# Primary_MCU.net
KiCad netlist of a schematic drawn in Altium Designer
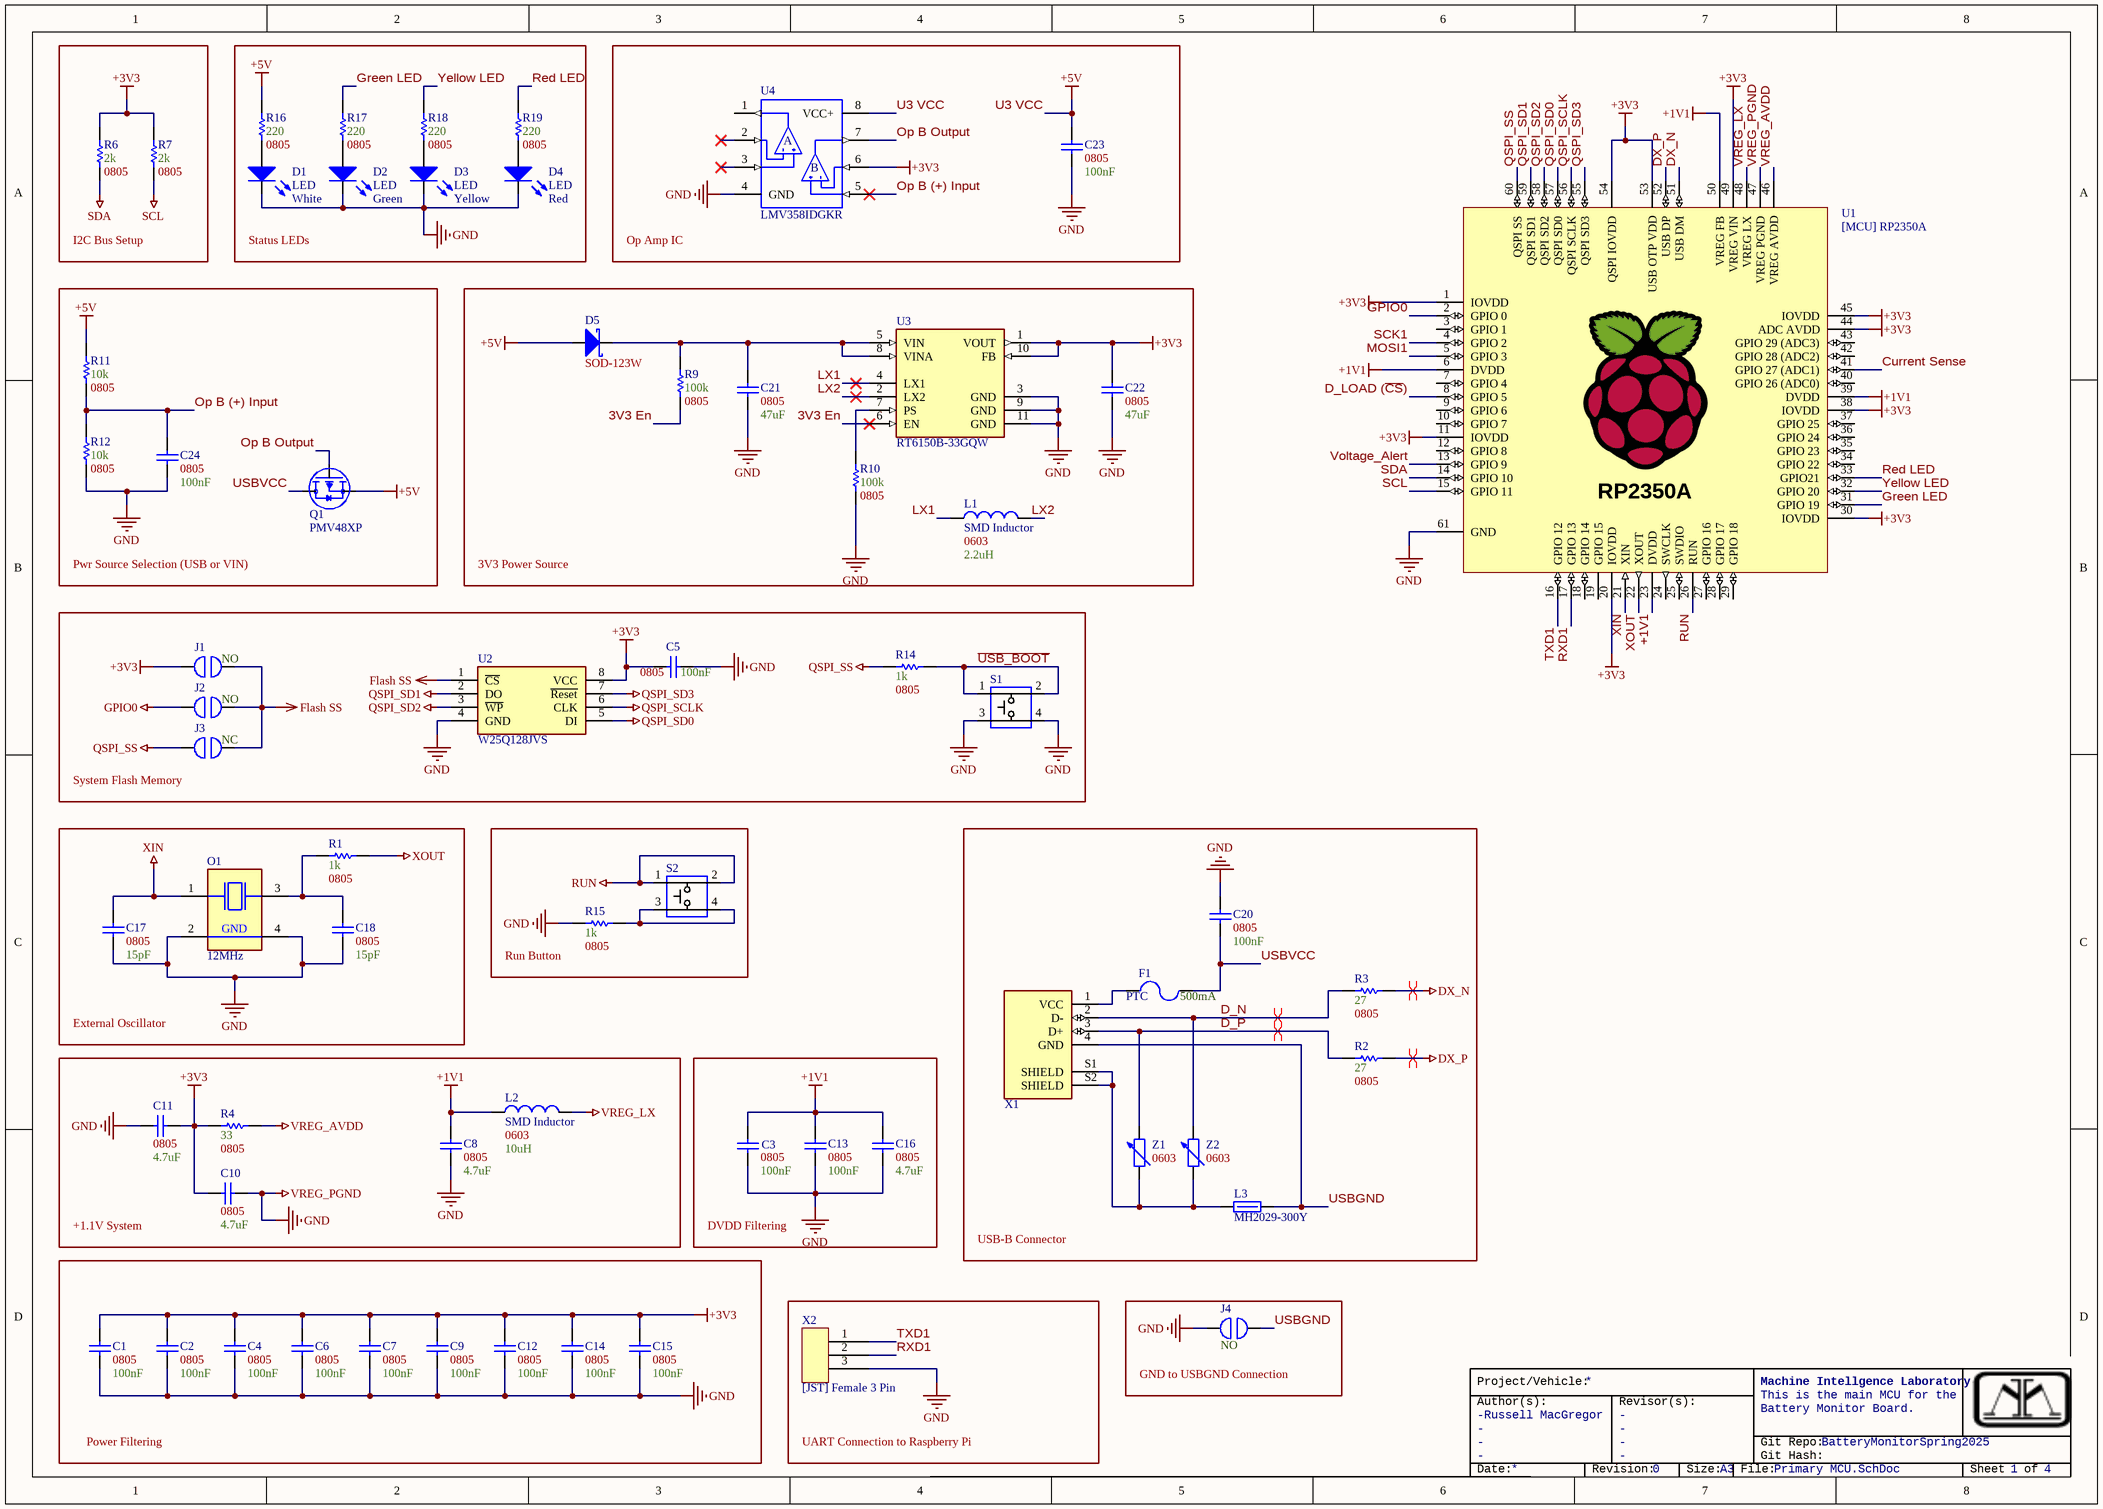
[diagram p0: Primary MCU.SchDoc]

(export (version "E")
  (design (tool "Eeschema 10.0.6"))
  (components
    (comp (ref "C1")
      (value "[Cap] SMD Nonpolarized")
      (footprint "[Cap] SMD 0805")
      (fields (field (name "SIZE PACKAGE") "0805") (field (name "CAPACITANCE") "100nF"))
      (libsource (lib "RADM Components") (part "[Cap] SMD Nonpolarized"))
    )
    (comp (ref "C2")
      (value "[Cap] SMD Nonpolarized")
      (footprint "[Cap] SMD 0805")
      (fields (field (name "SIZE PACKAGE") "0805") (field (name "CAPACITANCE") "100nF"))
      (libsource (lib "RADM Components") (part "[Cap] SMD Nonpolarized"))
    )
    (comp (ref "C3")
      (value "[Cap] SMD Nonpolarized")
      (footprint "[Cap] SMD 0805")
      (fields (field (name "SIZE PACKAGE") "0805") (field (name "CAPACITANCE") "100nF"))
      (libsource (lib "RADM Components") (part "[Cap] SMD Nonpolarized"))
    )
    (comp (ref "C4")
      (value "[Cap] SMD Nonpolarized")
      (footprint "[Cap] SMD 0805")
      (fields (field (name "SIZE PACKAGE") "0805") (field (name "CAPACITANCE") "100nF"))
      (libsource (lib "RADM Components") (part "[Cap] SMD Nonpolarized"))
    )
    (comp (ref "C5")
      (value "[Cap] SMD Nonpolarized")
      (footprint "[Cap] SMD 0805")
      (fields (field (name "SIZE PACKAGE") "0805") (field (name "CAPACITANCE") "100nF"))
      (libsource (lib "RADM Components") (part "[Cap] SMD Nonpolarized"))
    )
    (comp (ref "C6")
      (value "[Cap] SMD Nonpolarized")
      (footprint "[Cap] SMD 0805")
      (fields (field (name "SIZE PACKAGE") "0805") (field (name "CAPACITANCE") "100nF"))
      (libsource (lib "RADM Components") (part "[Cap] SMD Nonpolarized"))
    )
    (comp (ref "C7")
      (value "[Cap] SMD Nonpolarized")
      (footprint "[Cap] SMD 0805")
      (fields (field (name "SIZE PACKAGE") "0805") (field (name "CAPACITANCE") "100nF"))
      (libsource (lib "RADM Components") (part "[Cap] SMD Nonpolarized"))
    )
    (comp (ref "C8")
      (value "[Cap] SMD Nonpolarized")
      (footprint "[Cap] SMD 0805")
      (fields (field (name "SIZE PACKAGE") "0805") (field (name "CAPACITANCE") "4.7uF"))
      (libsource (lib "RADM Components") (part "[Cap] SMD Nonpolarized"))
    )
    (comp (ref "C9")
      (value "[Cap] SMD Nonpolarized")
      (footprint "[Cap] SMD 0805")
      (fields (field (name "SIZE PACKAGE") "0805") (field (name "CAPACITANCE") "100nF"))
      (libsource (lib "RADM Components") (part "[Cap] SMD Nonpolarized"))
    )
    (comp (ref "C10")
      (value "[Cap] SMD Nonpolarized")
      (footprint "[Cap] SMD 0805")
      (fields (field (name "SIZE PACKAGE") "0805") (field (name "CAPACITANCE") "4.7uF"))
      (libsource (lib "RADM Components") (part "[Cap] SMD Nonpolarized"))
    )
    (comp (ref "C11")
      (value "[Cap] SMD Nonpolarized")
      (footprint "[Cap] SMD 0805")
      (fields (field (name "SIZE PACKAGE") "0805") (field (name "CAPACITANCE") "4.7uF"))
      (libsource (lib "RADM Components") (part "[Cap] SMD Nonpolarized"))
    )
    (comp (ref "C12")
      (value "[Cap] SMD Nonpolarized")
      (footprint "[Cap] SMD 0805")
      (fields (field (name "SIZE PACKAGE") "0805") (field (name "CAPACITANCE") "100nF"))
      (libsource (lib "RADM Components") (part "[Cap] SMD Nonpolarized"))
    )
    (comp (ref "C13")
      (value "[Cap] SMD Nonpolarized")
      (footprint "[Cap] SMD 0805")
      (fields (field (name "SIZE PACKAGE") "0805") (field (name "CAPACITANCE") "100nF"))
      (libsource (lib "RADM Components") (part "[Cap] SMD Nonpolarized"))
    )
    (comp (ref "C14")
      (value "[Cap] SMD Nonpolarized")
      (footprint "[Cap] SMD 0805")
      (fields (field (name "SIZE PACKAGE") "0805") (field (name "CAPACITANCE") "100nF"))
      (libsource (lib "RADM Components") (part "[Cap] SMD Nonpolarized"))
    )
    (comp (ref "C15")
      (value "[Cap] SMD Nonpolarized")
      (footprint "[Cap] SMD 0805")
      (fields (field (name "SIZE PACKAGE") "0805") (field (name "CAPACITANCE") "100nF"))
      (libsource (lib "RADM Components") (part "[Cap] SMD Nonpolarized"))
    )
    (comp (ref "C16")
      (value "[Cap] SMD Nonpolarized")
      (footprint "[Cap] SMD 0805")
      (fields (field (name "SIZE PACKAGE") "0805") (field (name "CAPACITANCE") "4.7uF"))
      (libsource (lib "RADM Components") (part "[Cap] SMD Nonpolarized"))
    )
    (comp (ref "C17")
      (value "[Cap] SMD Nonpolarized")
      (footprint "[Cap] SMD 0805")
      (fields (field (name "SIZE PACKAGE") "0805") (field (name "CAPACITANCE") "15pF"))
      (libsource (lib "RADM Components") (part "[Cap] SMD Nonpolarized"))
    )
    (comp (ref "C18")
      (value "[Cap] SMD Nonpolarized")
      (footprint "[Cap] SMD 0805")
      (fields (field (name "SIZE PACKAGE") "0805") (field (name "CAPACITANCE") "15pF"))
      (libsource (lib "RADM Components") (part "[Cap] SMD Nonpolarized"))
    )
    (comp (ref "C20")
      (value "[Cap] SMD Nonpolarized")
      (footprint "[Cap] SMD 0805")
      (fields (field (name "SIZE PACKAGE") "0805") (field (name "CAPACITANCE") "100nF"))
      (libsource (lib "RADM Components") (part "[Cap] SMD Nonpolarized"))
    )
    (comp (ref "C21")
      (value "[Cap] SMD Nonpolarized")
      (footprint "[Cap] SMD 0805")
      (fields (field (name "SIZE PACKAGE") "0805") (field (name "CAPACITANCE") "47uF"))
      (libsource (lib "RADM Components") (part "[Cap] SMD Nonpolarized"))
    )
    (comp (ref "C22")
      (value "[Cap] SMD Nonpolarized")
      (footprint "[Cap] SMD 0805")
      (fields (field (name "SIZE PACKAGE") "0805") (field (name "CAPACITANCE") "47uF"))
      (libsource (lib "RADM Components") (part "[Cap] SMD Nonpolarized"))
    )
    (comp (ref "C23")
      (value "[Cap] SMD Nonpolarized")
      (footprint "[Cap] SMD 0805")
      (fields (field (name "SIZE PACKAGE") "0805") (field (name "CAPACITANCE") "100nF"))
      (libsource (lib "RADM Components") (part "[Cap] SMD Nonpolarized"))
    )
    (comp (ref "C24")
      (value "[Cap] SMD Nonpolarized")
      (footprint "[Cap] SMD 0805")
      (fields (field (name "SIZE PACKAGE") "0805") (field (name "CAPACITANCE") "100nF"))
      (libsource (lib "RADM Components") (part "[Cap] SMD Nonpolarized"))
    )
    (comp (ref "D1")
      (value "LED")
      (footprint "[LED] Thru-Hole, 3mm, White")
      (description "3mm LED")
      (fields (field (name "COLOR") "White"))
      (libsource (lib "RADM Components") (part "[LED] Thru-Hole 3mm"))
    )
    (comp (ref "D2")
      (value "LED")
      (footprint "[LED] Thru-Hole, 3mm, Green")
      (description "3mm LED")
      (fields (field (name "COLOR") "Green"))
      (libsource (lib "RADM Components") (part "[LED] Thru-Hole 3mm"))
    )
    (comp (ref "D3")
      (value "LED")
      (footprint "[LED] Thru-Hole, 3mm, Yellow")
      (description "3mm LED")
      (fields (field (name "COLOR") "Yellow"))
      (libsource (lib "RADM Components") (part "[LED] Thru-Hole 3mm"))
    )
    (comp (ref "D4")
      (value "LED")
      (footprint "[LED] Thru-Hole, 3mm, Red")
      (description "3mm LED")
      (fields (field (name "COLOR") "Red"))
      (libsource (lib "RADM Components") (part "[LED] Thru-Hole 3mm"))
    )
    (comp (ref "D5")
      (value "Schottky")
      (footprint "[Diode] SMD SOD-123W")
      (description "PMEG6010ELR")
      (fields (field (name "SIZE PACKAGE") "SOD-123W"))
      (libsource (lib "RADM Components") (part "[Diode] SMD Schottky"))
    )
    (comp (ref "F1")
      (value "PTC")
      (footprint "[PTC] 500mA Trip")
      (description "MF-MSMF050-2\r\nJLC Part #: C17313")
      (fields (field (name "JLC PART #") "C17313") (field (name "TRIP CURRENT") "500mA"))
      (libsource (lib "RADM Components") (part "[PTC] 500mA Trip"))
    )
    (comp (ref "J1")
      (value "[Jump] SMD Jumper")
      (footprint "[Jumper] Solderable Jumper")
      (description "Solderable jumper")
      (fields (field (name "NO/NC") "NO"))
      (libsource (lib "RADM Components") (part "[Jump] SMD Jumper"))
    )
    (comp (ref "J2")
      (value "[Jump] SMD Jumper")
      (footprint "[Jumper] Solderable Jumper")
      (description "Solderable jumper")
      (fields (field (name "NO/NC") "NO"))
      (libsource (lib "RADM Components") (part "[Jump] SMD Jumper"))
    )
    (comp (ref "J3")
      (value "[Jump] SMD Jumper")
      (footprint "[Jumper] Solderable Jumper")
      (description "Solderable jumper")
      (fields (field (name "NO/NC") "NC"))
      (libsource (lib "RADM Components") (part "[Jump] SMD Jumper"))
    )
    (comp (ref "J4")
      (value "[Jump] SMD Jumper")
      (footprint "[Jumper] Solderable Jumper")
      (description "Solderable jumper")
      (fields (field (name "NO/NC") "NO"))
      (libsource (lib "RADM Components") (part "[Jump] SMD Jumper"))
    )
    (comp (ref "L1")
      (value "SMD Inductor")
      (footprint "[Inductor] SMD 0603")
      (fields (field (name "SIZE PACKAGE") "0603") (field (name "INDUCTANCE") "2.2uH"))
      (libsource (lib "RADM Components") (part "[Inductor] SMD Inductor"))
    )
    (comp (ref "L2")
      (value "SMD Inductor")
      (footprint "[Inductor] SMD 0603")
      (fields (field (name "SIZE PACKAGE") "0603") (field (name "INDUCTANCE") "10uH"))
      (libsource (lib "RADM Components") (part "[Inductor] SMD Inductor"))
    )
    (comp (ref "L3")
      (value "MH2029-300Y")
      (footprint "[Ferrite] SMD Bead 0805 (1)")
      (description "652-MH2029-300Y")
      (libsource (lib "RADM Components") (part "[Ferrite] SMD Ferrite Bead (1)"))
    )
    (comp (ref "O1")
      (value "12MHz")
      (footprint "[XTAL] SMD 12MHz")
      (description "815-ABM8-272-T3")
      (libsource (lib "RADM Components") (part "[XTAL] SMD 12MHz"))
    )
    (comp (ref "Q1")
      (value "PMV48XP")
      (footprint "[FET] P-Channel Mosfet")
      (fields (field (name "JLC PART #") "C2959854"))
      (libsource (lib "RADM Components") (part "[FET] P-Channel MOSFET"))
    )
    (comp (ref "R1")
      (value "[Res] SMD Resistor")
      (footprint "[Res] SMD 0805")
      (fields (field (name "RESISTANCE") "1k") (field (name "SIZE PACKAGE") "0805"))
      (libsource (lib "RADM Components") (part "[Res] SMD Resistor"))
    )
    (comp (ref "R2")
      (value "[Res] SMD Resistor")
      (footprint "[Res] SMD 0805")
      (fields (field (name "RESISTANCE") "27") (field (name "SIZE PACKAGE") "0805"))
      (libsource (lib "RADM Components") (part "[Res] SMD Resistor"))
    )
    (comp (ref "R3")
      (value "[Res] SMD Resistor")
      (footprint "[Res] SMD 0805")
      (fields (field (name "RESISTANCE") "27") (field (name "SIZE PACKAGE") "0805"))
      (libsource (lib "RADM Components") (part "[Res] SMD Resistor"))
    )
    (comp (ref "R4")
      (value "[Res] SMD Resistor")
      (footprint "[Res] SMD 0805")
      (fields (field (name "RESISTANCE") "33") (field (name "SIZE PACKAGE") "0805"))
      (libsource (lib "RADM Components") (part "[Res] SMD Resistor"))
    )
    (comp (ref "R6")
      (value "[Res] SMD Resistor")
      (footprint "[Res] SMD 0805")
      (fields (field (name "RESISTANCE") "2k") (field (name "SIZE PACKAGE") "0805"))
      (libsource (lib "RADM Components") (part "[Res] SMD Resistor"))
    )
    (comp (ref "R7")
      (value "[Res] SMD Resistor")
      (footprint "[Res] SMD 0805")
      (fields (field (name "RESISTANCE") "2k") (field (name "SIZE PACKAGE") "0805"))
      (libsource (lib "RADM Components") (part "[Res] SMD Resistor"))
    )
    (comp (ref "R9")
      (value "[Res] SMD Resistor")
      (footprint "[Res] SMD 0805")
      (fields (field (name "RESISTANCE") "100k") (field (name "SIZE PACKAGE") "0805"))
      (libsource (lib "RADM Components") (part "[Res] SMD Resistor"))
    )
    (comp (ref "R10")
      (value "[Res] SMD Resistor")
      (footprint "[Res] SMD 0805")
      (fields (field (name "RESISTANCE") "100k") (field (name "SIZE PACKAGE") "0805"))
      (libsource (lib "RADM Components") (part "[Res] SMD Resistor"))
    )
    (comp (ref "R11")
      (value "[Res] SMD Resistor")
      (footprint "[Res] SMD 0805")
      (fields (field (name "RESISTANCE") "10k") (field (name "SIZE PACKAGE") "0805"))
      (libsource (lib "RADM Components") (part "[Res] SMD Resistor"))
    )
    (comp (ref "R12")
      (value "[Res] SMD Resistor")
      (footprint "[Res] SMD 0805")
      (fields (field (name "RESISTANCE") "10k") (field (name "SIZE PACKAGE") "0805"))
      (libsource (lib "RADM Components") (part "[Res] SMD Resistor"))
    )
    (comp (ref "R14")
      (value "[Res] SMD Resistor")
      (footprint "[Res] SMD 0805")
      (fields (field (name "RESISTANCE") "1k") (field (name "SIZE PACKAGE") "0805"))
      (libsource (lib "RADM Components") (part "[Res] SMD Resistor"))
    )
    (comp (ref "R15")
      (value "[Res] SMD Resistor")
      (footprint "[Res] SMD 0805")
      (fields (field (name "RESISTANCE") "1k") (field (name "SIZE PACKAGE") "0805"))
      (libsource (lib "RADM Components") (part "[Res] SMD Resistor"))
    )
    (comp (ref "R16")
      (value "[Res] SMD Resistor")
      (footprint "[Res] SMD 0805")
      (fields (field (name "RESISTANCE") "220") (field (name "SIZE PACKAGE") "0805"))
      (libsource (lib "RADM Components") (part "[Res] SMD Resistor"))
    )
    (comp (ref "R17")
      (value "[Res] SMD Resistor")
      (footprint "[Res] SMD 0805")
      (fields (field (name "RESISTANCE") "220") (field (name "SIZE PACKAGE") "0805"))
      (libsource (lib "RADM Components") (part "[Res] SMD Resistor"))
    )
    (comp (ref "R18")
      (value "[Res] SMD Resistor")
      (footprint "[Res] SMD 0805")
      (fields (field (name "RESISTANCE") "220") (field (name "SIZE PACKAGE") "0805"))
      (libsource (lib "RADM Components") (part "[Res] SMD Resistor"))
    )
    (comp (ref "R19")
      (value "[Res] SMD Resistor")
      (footprint "[Res] SMD 0805")
      (fields (field (name "RESISTANCE") "220") (field (name "SIZE PACKAGE") "0805"))
      (libsource (lib "RADM Components") (part "[Res] SMD Resistor"))
    )
    (comp (ref "S1")
      (value "Standard pushbutton")
      (footprint "[Switch] Pushbutton")
      (libsource (lib "RADM Components") (part "[Switch] Pushbutton"))
    )
    (comp (ref "S2")
      (value "Standard pushbutton")
      (footprint "[Switch] Pushbutton")
      (libsource (lib "RADM Components") (part "[Switch] Pushbutton"))
    )
    (comp (ref "U1")
      (value "[MCU] RP2350A")
      (footprint "[MCU] RP2350A")
      (libsource (lib "RADM Components") (part "[MCU] RP2350A"))
    )
    (comp (ref "U2")
      (value "W25Q128JVS")
      (footprint "[IC] 16Mb Flash Memory")
      (description "W25Q128JVSIQ TR")
      (libsource (lib "RADM Components") (part "[IC] 16Mb Flash Memory"))
    )
    (comp (ref "U3")
      (value "RT6150B-33GQW")
      (footprint "[IC] 3V3 Regulator (2)")
      (libsource (lib "RADM Components") (part "[IC] 3V3 Regulator (2)"))
    )
    (comp (ref "U4")
      (value "LMV358IDGKR")
      (footprint "[IC] Dual Op-Ap")
      (fields (field (name "JLC PART #") "C105242"))
      (libsource (lib "RADM Components") (part "[IC] Dual Op-Amp"))
    )
    (comp (ref "X1")
      (value "[Port] USB Type-B Female (Thru-Hole)")
      (footprint "[Port] USB Type-B Thru-Hole")
      (description "USB-B-S-F-B-TH")
      (fields (field (name "JLC PART #") "C5714571"))
      (libsource (lib "RADM Components") (part "[Port] USB Type-B Female (Thru-Hole)"))
    )
    (comp (ref "X2")
      (value "[JST] Female 3 Pin")
      (footprint "[JST] 3PIN")
      (libsource (lib "RADM Components") (part "[JST] Female 3 Pin"))
    )
    (comp (ref "Z1")
      (value "[Inductor] SMD Varistor")
      (footprint "[Inductor] SMD Varistor 0603")
      (fields (field (name "JLC PART #") "C840634") (field (name "SIZE PACKAGE") "0603"))
      (libsource (lib "RADM Components") (part "[Inductor] SMD Varistor"))
    )
    (comp (ref "Z2")
      (value "[Inductor] SMD Varistor")
      (footprint "[Inductor] SMD Varistor 0603")
      (fields (field (name "JLC PART #") "C840634") (field (name "SIZE PACKAGE") "0603"))
      (libsource (lib "RADM Components") (part "[Inductor] SMD Varistor"))
    )
  )
  (nets
    (net (code "1") (name "+1V1") (class "Default")
      (node (ref "C13") (pin "2") (pinfunction "2_2") (pintype "passive"))
      (node (ref "C16") (pin "2") (pinfunction "2_2") (pintype "passive"))
      (node (ref "C3") (pin "2") (pinfunction "2_2") (pintype "passive"))
      (node (ref "C8") (pin "2") (pinfunction "2_2") (pintype "passive"))
      (node (ref "L2") (pin "1") (pinfunction "1_1") (pintype "passive"))
      (node (ref "U1") (pin "23") (pinfunction "DVDD_23") (pintype "power_in"))
      (node (ref "U1") (pin "39") (pinfunction "DVDD_39") (pintype "power_in"))
      (node (ref "U1") (pin "50") (pinfunction "VREG_FB_50") (pintype "power_in"))
      (node (ref "U1") (pin "6") (pinfunction "DVDD_6") (pintype "power_in"))
    )
    (net (code "2") (name "+3V3") (class "Default")
      (node (ref "C1") (pin "2") (pinfunction "2_2") (pintype "passive"))
      (node (ref "C10") (pin "2") (pinfunction "2_2") (pintype "passive"))
      (node (ref "C11") (pin "1") (pinfunction "1_1") (pintype "passive"))
      (node (ref "C12") (pin "2") (pinfunction "2_2") (pintype "passive"))
      (node (ref "C14") (pin "2") (pinfunction "2_2") (pintype "passive"))
      (node (ref "C15") (pin "2") (pinfunction "2_2") (pintype "passive"))
      (node (ref "C2") (pin "2") (pinfunction "2_2") (pintype "passive"))
      (node (ref "C22") (pin "2") (pinfunction "2_2") (pintype "passive"))
      (node (ref "C4") (pin "2") (pinfunction "2_2") (pintype "passive"))
      (node (ref "C5") (pin "2") (pinfunction "2_2") (pintype "passive"))
      (node (ref "C6") (pin "2") (pinfunction "2_2") (pintype "passive"))
      (node (ref "C7") (pin "2") (pinfunction "2_2") (pintype "passive"))
      (node (ref "C9") (pin "2") (pinfunction "2_2") (pintype "passive"))
      (node (ref "J1") (pin "1") (pintype "passive"))
      (node (ref "R4") (pin "2") (pinfunction "2_2") (pintype "passive"))
      (node (ref "R6") (pin "2") (pinfunction "2_2") (pintype "passive"))
      (node (ref "R7") (pin "2") (pinfunction "2_2") (pintype "passive"))
      (node (ref "U1") (pin "1") (pinfunction "IOVDD_1") (pintype "power_in"))
      (node (ref "U1") (pin "11") (pinfunction "IOVDD_11") (pintype "power_in"))
      (node (ref "U1") (pin "20") (pinfunction "IOVDD_20") (pintype "power_in"))
      (node (ref "U1") (pin "30") (pinfunction "IOVDD_30") (pintype "power_in"))
      (node (ref "U1") (pin "38") (pinfunction "IOVDD_38") (pintype "power_in"))
      (node (ref "U1") (pin "44") (pinfunction "ADC_AVDD_44") (pintype "power_in"))
      (node (ref "U1") (pin "45") (pinfunction "IOVDD_45") (pintype "power_in"))
      (node (ref "U1") (pin "49") (pinfunction "VREG_VIN_49") (pintype "power_in"))
      (node (ref "U1") (pin "53") (pinfunction "USB_OTP_VDD_53") (pintype "power_in"))
      (node (ref "U1") (pin "54") (pinfunction "QSPI_IOVDD_54") (pintype "power_in"))
      (node (ref "U2") (pin "8") (pinfunction "VCC_8") (pintype "passive"))
      (node (ref "U3") (pin "1") (pinfunction "VOUT_1") (pintype "output"))
      (node (ref "U3") (pin "10") (pinfunction "FB_10") (pintype "input"))
      (node (ref "U4") (pin "6") (pinfunction "2IN-_6") (pintype "input"))
    )
    (net (code "3") (name "+5V") (class "Default")
      (node (ref "C23") (pin "2") (pinfunction "2_2") (pintype "passive"))
      (node (ref "D5") (pin "2") (pinfunction "A_2") (pintype "power_in"))
      (node (ref "Q1") (pin "2") (pinfunction "S_2") (pintype "passive"))
      (node (ref "R11") (pin "2") (pinfunction "2_2") (pintype "passive"))
      (node (ref "R16") (pin "1") (pinfunction "1_1") (pintype "passive"))
      (node (ref "U4") (pin "8") (pinfunction "VCC+_8") (pintype "power_in"))
    )
    (net (code "4") (name "/3V3 En") (class "Default")
      (node (ref "R9") (pin "1") (pinfunction "1_1") (pintype "passive"))
      (node (ref "U3") (pin "6") (pinfunction "EN_6") (pintype "input"))
    )
    (net (code "5") (name "/Current Sense") (class "Default")
      (node (ref "U1") (pin "41") (pinfunction "GPIO_27_(ADC1)_41") (pintype "bidirectional"))
    )
    (net (code "6") (name "/D_LOAD (~{CS})") (class "Default")
      (node (ref "U1") (pin "8") (pinfunction "GPIO_5_8") (pintype "bidirectional"))
    )
    (net (code "7") (name "/D_N") (class "Default")
      (node (ref "R3") (pin "2") (pinfunction "2_2") (pintype "passive"))
      (node (ref "X1") (pin "2") (pinfunction "D-_2") (pintype "bidirectional"))
      (node (ref "Z2") (pin "2") (pinfunction "2_2") (pintype "passive"))
    )
    (net (code "8") (name "/D_P") (class "Default")
      (node (ref "R2") (pin "2") (pinfunction "2_2") (pintype "passive"))
      (node (ref "X1") (pin "3") (pinfunction "D+_3") (pintype "bidirectional"))
      (node (ref "Z1") (pin "2") (pinfunction "2_2") (pintype "passive"))
    )
    (net (code "9") (name "/Green LED") (class "Default")
      (node (ref "R17") (pin "1") (pinfunction "1_1") (pintype "passive"))
      (node (ref "U1") (pin "31") (pinfunction "GPIO_19_31") (pintype "bidirectional"))
    )
    (net (code "10") (name "/LX1") (class "Default")
      (node (ref "L1") (pin "1") (pinfunction "1_1") (pintype "passive"))
      (node (ref "U3") (pin "4") (pinfunction "LX1_4") (pintype "power_in"))
    )
    (net (code "11") (name "/LX2") (class "Default")
      (node (ref "L1") (pin "2") (pinfunction "2_2") (pintype "passive"))
      (node (ref "U3") (pin "2") (pinfunction "LX2_2") (pintype "power_in"))
    )
    (net (code "12") (name "/MOSI1") (class "Default")
      (node (ref "U1") (pin "5") (pinfunction "GPIO_3_5") (pintype "bidirectional"))
    )
    (net (code "13") (name "/Op B (+) Input") (class "Default")
      (node (ref "C24") (pin "2") (pinfunction "2_2") (pintype "passive"))
      (node (ref "R11") (pin "1") (pinfunction "1_1") (pintype "passive"))
      (node (ref "R12") (pin "2") (pinfunction "2_2") (pintype "passive"))
      (node (ref "U4") (pin "5") (pinfunction "2IN+_5") (pintype "input"))
    )
    (net (code "14") (name "/Op B Output") (class "Default")
      (node (ref "Q1") (pin "1") (pinfunction "G_1") (pintype "passive"))
      (node (ref "U4") (pin "7") (pinfunction "2OUT_7") (pintype "output"))
    )
    (net (code "15") (name "/RXD1") (class "Default")
      (node (ref "U1") (pin "17") (pinfunction "GPIO_13_17") (pintype "bidirectional"))
      (node (ref "X2") (pin "2") (pintype "passive"))
    )
    (net (code "16") (name "/Red LED") (class "Default")
      (node (ref "R19") (pin "1") (pinfunction "1_1") (pintype "passive"))
      (node (ref "U1") (pin "33") (pinfunction "GPIO21_33") (pintype "bidirectional"))
    )
    (net (code "17") (name "/SCK1") (class "Default")
      (node (ref "U1") (pin "4") (pinfunction "GPIO_2_4") (pintype "bidirectional"))
    )
    (net (code "18") (name "/TXD1") (class "Default")
      (node (ref "U1") (pin "16") (pinfunction "GPIO_12_16") (pintype "bidirectional"))
      (node (ref "X2") (pin "1") (pintype "passive"))
    )
    (net (code "19") (name "/USBGND") (class "Default")
      (node (ref "J4") (pin "2") (pintype "passive"))
      (node (ref "L3") (pin "2") (pinfunction "2_2") (pintype "passive"))
      (node (ref "X1") (pin "4") (pinfunction "GND_4") (pintype "power_in"))
    )
    (net (code "20") (name "/USBVCC") (class "Default")
      (node (ref "C20") (pin "1") (pinfunction "1_1") (pintype "passive"))
      (node (ref "F1") (pin "2") (pinfunction "2_2") (pintype "passive"))
      (node (ref "Q1") (pin "3") (pinfunction "D_3") (pintype "passive"))
    )
    (net (code "21") (name "/Voltage_Alert") (class "Default")
      (node (ref "U1") (pin "13") (pinfunction "GPIO_9_13") (pintype "bidirectional"))
    )
    (net (code "22") (name "/Yellow LED") (class "Default")
      (node (ref "R18") (pin "1") (pinfunction "1_1") (pintype "passive"))
      (node (ref "U1") (pin "32") (pinfunction "GPIO_20_32") (pintype "bidirectional"))
    )
    (net (code "23") (name "/~{USB_BOOT}") (class "Default")
      (node (ref "R14") (pin "1") (pinfunction "1_1") (pintype "passive"))
      (node (ref "S1") (pin "1") (pintype "power_in"))
      (node (ref "S1") (pin "2") (pintype "power_in"))
    )
    (net (code "24") (name "DX_N") (class "Default")
      (node (ref "R3") (pin "1") (pinfunction "1_1") (pintype "passive"))
      (node (ref "U1") (pin "51") (pinfunction "USB_DM_51") (pintype "bidirectional"))
    )
    (net (code "25") (name "DX_P") (class "Default")
      (node (ref "R2") (pin "1") (pinfunction "1_1") (pintype "passive"))
      (node (ref "U1") (pin "52") (pinfunction "USB_DP_52") (pintype "bidirectional"))
    )
    (net (code "26") (name "Flash SS") (class "Default")
      (node (ref "J1") (pin "2") (pintype "passive"))
      (node (ref "J2") (pin "2") (pintype "passive"))
      (node (ref "J3") (pin "2") (pintype "passive"))
      (node (ref "U2") (pin "1") (pinfunction "~{CS}_1") (pintype "passive"))
    )
    (net (code "27") (name "GND") (class "Default")
      (node (ref "C1") (pin "1") (pinfunction "1_1") (pintype "passive"))
      (node (ref "C10") (pin "1") (pinfunction "1_1") (pintype "passive"))
      (node (ref "C11") (pin "2") (pinfunction "2_2") (pintype "passive"))
      (node (ref "C12") (pin "1") (pinfunction "1_1") (pintype "passive"))
      (node (ref "C13") (pin "1") (pinfunction "1_1") (pintype "passive"))
      (node (ref "C14") (pin "1") (pinfunction "1_1") (pintype "passive"))
      (node (ref "C15") (pin "1") (pinfunction "1_1") (pintype "passive"))
      (node (ref "C16") (pin "1") (pinfunction "1_1") (pintype "passive"))
      (node (ref "C17") (pin "1") (pinfunction "1_1") (pintype "passive"))
      (node (ref "C18") (pin "1") (pinfunction "1_1") (pintype "passive"))
      (node (ref "C2") (pin "1") (pinfunction "1_1") (pintype "passive"))
      (node (ref "C20") (pin "2") (pinfunction "2_2") (pintype "passive"))
      (node (ref "C21") (pin "1") (pinfunction "1_1") (pintype "passive"))
      (node (ref "C22") (pin "1") (pinfunction "1_1") (pintype "passive"))
      (node (ref "C23") (pin "1") (pinfunction "1_1") (pintype "passive"))
      (node (ref "C24") (pin "1") (pinfunction "1_1") (pintype "passive"))
      (node (ref "C3") (pin "1") (pinfunction "1_1") (pintype "passive"))
      (node (ref "C4") (pin "1") (pinfunction "1_1") (pintype "passive"))
      (node (ref "C5") (pin "1") (pinfunction "1_1") (pintype "passive"))
      (node (ref "C6") (pin "1") (pinfunction "1_1") (pintype "passive"))
      (node (ref "C7") (pin "1") (pinfunction "1_1") (pintype "passive"))
      (node (ref "C8") (pin "1") (pinfunction "1_1") (pintype "passive"))
      (node (ref "C9") (pin "1") (pinfunction "1_1") (pintype "passive"))
      (node (ref "D1") (pin "2") (pinfunction "K_2") (pintype "passive"))
      (node (ref "D2") (pin "2") (pinfunction "K_2") (pintype "passive"))
      (node (ref "D3") (pin "2") (pinfunction "K_2") (pintype "passive"))
      (node (ref "D4") (pin "2") (pinfunction "K_2") (pintype "passive"))
      (node (ref "J4") (pin "1") (pintype "passive"))
      (node (ref "O1") (pin "2") (pinfunction "GND_2") (pintype "power_in"))
      (node (ref "O1") (pin "4") (pinfunction "GND_4") (pintype "power_in"))
      (node (ref "R10") (pin "1") (pinfunction "1_1") (pintype "passive"))
      (node (ref "R12") (pin "1") (pinfunction "1_1") (pintype "passive"))
      (node (ref "R15") (pin "2") (pinfunction "2_2") (pintype "passive"))
      (node (ref "S1") (pin "3") (pintype "power_in"))
      (node (ref "S1") (pin "4") (pintype "power_in"))
      (node (ref "U1") (pin "47") (pinfunction "VREG_PGND_47") (pintype "power_in"))
      (node (ref "U1") (pin "61") (pinfunction "GND_61") (pintype "power_in"))
      (node (ref "U2") (pin "4") (pinfunction "GND_4") (pintype "passive"))
      (node (ref "U3") (pin "11") (pinfunction "GND_11") (pintype "power_in"))
      (node (ref "U3") (pin "3") (pinfunction "GND_3") (pintype "power_in"))
      (node (ref "U3") (pin "9") (pinfunction "GND_9") (pintype "power_in"))
      (node (ref "U4") (pin "4") (pinfunction "GND_4") (pintype "power_in"))
      (node (ref "X2") (pin "3") (pintype "passive"))
    )
    (net (code "28") (name "GPIO0") (class "Default")
      (node (ref "J2") (pin "1") (pintype "passive"))
      (node (ref "U1") (pin "2") (pinfunction "GPIO_0_2") (pintype "bidirectional"))
    )
    (net (code "29") (name "Net-(D1-A)") (class "Default")
      (node (ref "D1") (pin "1") (pinfunction "A_1") (pintype "passive"))
      (node (ref "R16") (pin "2") (pinfunction "2_2") (pintype "passive"))
    )
    (net (code "30") (name "Net-(D2-A)") (class "Default")
      (node (ref "D2") (pin "1") (pinfunction "A_1") (pintype "passive"))
      (node (ref "R17") (pin "2") (pinfunction "2_2") (pintype "passive"))
    )
    (net (code "31") (name "Net-(D3-A)") (class "Default")
      (node (ref "D3") (pin "1") (pinfunction "A_1") (pintype "passive"))
      (node (ref "R18") (pin "2") (pinfunction "2_2") (pintype "passive"))
    )
    (net (code "32") (name "Net-(D4-A)") (class "Default")
      (node (ref "D4") (pin "1") (pinfunction "A_1") (pintype "passive"))
      (node (ref "R19") (pin "2") (pinfunction "2_2") (pintype "passive"))
    )
    (net (code "33") (name "Net-(D5-K)") (class "Default")
      (node (ref "C21") (pin "2") (pinfunction "2_2") (pintype "passive"))
      (node (ref "D5") (pin "1") (pinfunction "K_1") (pintype "power_in"))
      (node (ref "R9") (pin "2") (pinfunction "2_2") (pintype "passive"))
      (node (ref "U3") (pin "5") (pinfunction "VIN_5") (pintype "input"))
      (node (ref "U3") (pin "8") (pinfunction "VINA_8") (pintype "input"))
    )
    (net (code "34") (name "Net-(L3-Pad1)") (class "Default")
      (node (ref "L3") (pin "1") (pinfunction "1_1") (pintype "passive"))
      (node (ref "X1") (pin "S1") (pinfunction "SHIELD_S1") (pintype "passive"))
      (node (ref "X1") (pin "S2") (pinfunction "SHIELD_S2") (pintype "passive"))
      (node (ref "Z1") (pin "1") (pinfunction "1_1") (pintype "passive"))
      (node (ref "Z2") (pin "1") (pinfunction "1_1") (pintype "passive"))
    )
    (net (code "35") (name "Net-(O1-XTAL2)") (class "Default")
      (node (ref "C18") (pin "2") (pinfunction "2_2") (pintype "passive"))
      (node (ref "O1") (pin "3") (pinfunction "XTAL2_3") (pintype "power_in"))
      (node (ref "R1") (pin "2") (pinfunction "2_2") (pintype "passive"))
    )
    (net (code "36") (name "Net-(R15-Pad1)") (class "Default")
      (node (ref "R15") (pin "1") (pinfunction "1_1") (pintype "passive"))
      (node (ref "S2") (pin "3") (pintype "power_in"))
      (node (ref "S2") (pin "4") (pintype "power_in"))
    )
    (net (code "37") (name "Net-(U3-PS)") (class "Default")
      (node (ref "R10") (pin "2") (pinfunction "2_2") (pintype "passive"))
      (node (ref "U3") (pin "7") (pinfunction "PS_7") (pintype "input"))
    )
    (net (code "38") (name "Net-(X1-VCC)") (class "Default")
      (node (ref "F1") (pin "1") (pinfunction "1_1") (pintype "passive"))
      (node (ref "X1") (pin "1") (pinfunction "VCC_1") (pintype "power_in"))
    )
    (net (code "39") (name "QSPI_SCLK") (class "Default")
      (node (ref "U1") (pin "56") (pinfunction "QSPI_SCLK_56") (pintype "bidirectional"))
      (node (ref "U2") (pin "6") (pinfunction "CLK_6") (pintype "passive"))
    )
    (net (code "40") (name "QSPI_SD0") (class "Default")
      (node (ref "U1") (pin "57") (pinfunction "QSPI_SD0_57") (pintype "bidirectional"))
      (node (ref "U2") (pin "5") (pinfunction "DI_5") (pintype "passive"))
    )
    (net (code "41") (name "QSPI_SD1") (class "Default")
      (node (ref "U1") (pin "59") (pinfunction "QSPI_SD1_59") (pintype "bidirectional"))
      (node (ref "U2") (pin "2") (pinfunction "DO_2") (pintype "passive"))
    )
    (net (code "42") (name "QSPI_SD2") (class "Default")
      (node (ref "U1") (pin "58") (pinfunction "QSPI_SD2_58") (pintype "bidirectional"))
      (node (ref "U2") (pin "3") (pinfunction "~{WP}_3") (pintype "passive"))
    )
    (net (code "43") (name "QSPI_SD3") (class "Default")
      (node (ref "U1") (pin "55") (pinfunction "QSPI_SD3_55") (pintype "bidirectional"))
      (node (ref "U2") (pin "7") (pinfunction "~{Reset}_7") (pintype "passive"))
    )
    (net (code "44") (name "QSPI_SS") (class "Default")
      (node (ref "J3") (pin "1") (pintype "passive"))
      (node (ref "R14") (pin "2") (pinfunction "2_2") (pintype "passive"))
      (node (ref "U1") (pin "60") (pinfunction "QSPI_SS_60") (pintype "bidirectional"))
    )
    (net (code "45") (name "RUN") (class "Default")
      (node (ref "S2") (pin "1") (pintype "power_in"))
      (node (ref "S2") (pin "2") (pintype "power_in"))
      (node (ref "U1") (pin "26") (pinfunction "RUN_26") (pintype "passive"))
    )
    (net (code "46") (name "SCL") (class "Default")
      (node (ref "R7") (pin "1") (pinfunction "1_1") (pintype "passive"))
      (node (ref "U1") (pin "15") (pinfunction "GPIO_11_15") (pintype "bidirectional"))
    )
    (net (code "47") (name "SDA") (class "Default")
      (node (ref "R6") (pin "1") (pinfunction "1_1") (pintype "passive"))
      (node (ref "U1") (pin "14") (pinfunction "GPIO_10_14") (pintype "bidirectional"))
    )
    (net (code "48") (name "VREG_AVDD") (class "Default")
      (node (ref "R4") (pin "1") (pinfunction "1_1") (pintype "passive"))
      (node (ref "U1") (pin "46") (pinfunction "VREG_AVDD_46") (pintype "power_in"))
    )
    (net (code "49") (name "VREG_LX") (class "Default")
      (node (ref "L2") (pin "2") (pinfunction "2_2") (pintype "passive"))
      (node (ref "U1") (pin "48") (pinfunction "VREG_LX_48") (pintype "power_in"))
    )
    (net (code "50") (name "XIN") (class "Default")
      (node (ref "C17") (pin "2") (pinfunction "2_2") (pintype "passive"))
      (node (ref "O1") (pin "1") (pinfunction "XTAL1_1") (pintype "power_in"))
      (node (ref "U1") (pin "21") (pinfunction "XIN_21") (pintype "input"))
    )
    (net (code "51") (name "XOUT") (class "Default")
      (node (ref "R1") (pin "1") (pinfunction "1_1") (pintype "passive"))
      (node (ref "U1") (pin "22") (pinfunction "XOUT_22") (pintype "output"))
    )
    (net (code "52") (name "unconnected-(U1-GPIO_1-Pad3)") (class "Default")
      (node (ref "U1") (pin "3") (pinfunction "GPIO_1_3") (pintype "bidirectional"))
    )
    (net (code "53") (name "unconnected-(U1-GPIO_4-Pad7)") (class "Default")
      (node (ref "U1") (pin "7") (pinfunction "GPIO_4_7") (pintype "bidirectional"))
    )
    (net (code "54") (name "unconnected-(U1-GPIO_6-Pad9)") (class "Default")
      (node (ref "U1") (pin "9") (pinfunction "GPIO_6_9") (pintype "bidirectional"))
    )
    (net (code "55") (name "unconnected-(U1-GPIO_7-Pad10)") (class "Default")
      (node (ref "U1") (pin "10") (pinfunction "GPIO_7_10") (pintype "bidirectional"))
    )
    (net (code "56") (name "unconnected-(U1-GPIO_8-Pad12)") (class "Default")
      (node (ref "U1") (pin "12") (pinfunction "GPIO_8_12") (pintype "bidirectional"))
    )
    (net (code "57") (name "unconnected-(U1-GPIO_14-Pad18)") (class "Default")
      (node (ref "U1") (pin "18") (pinfunction "GPIO_14_18") (pintype "bidirectional"))
    )
    (net (code "58") (name "unconnected-(U1-GPIO_15-Pad19)") (class "Default")
      (node (ref "U1") (pin "19") (pinfunction "GPIO_15_19") (pintype "power_in"))
    )
    (net (code "59") (name "unconnected-(U1-GPIO_16-Pad27)") (class "Default")
      (node (ref "U1") (pin "27") (pinfunction "GPIO_16_27") (pintype "bidirectional"))
    )
    (net (code "60") (name "unconnected-(U1-GPIO_17-Pad28)") (class "Default")
      (node (ref "U1") (pin "28") (pinfunction "GPIO_17_28") (pintype "bidirectional"))
    )
    (net (code "61") (name "unconnected-(U1-GPIO_18-Pad29)") (class "Default")
      (node (ref "U1") (pin "29") (pinfunction "GPIO_18_29") (pintype "bidirectional"))
    )
    (net (code "62") (name "unconnected-(U1-GPIO_22-Pad34)") (class "Default")
      (node (ref "U1") (pin "34") (pinfunction "GPIO_22_34") (pintype "bidirectional"))
    )
    (net (code "63") (name "unconnected-(U1-GPIO_23-Pad35)") (class "Default")
      (node (ref "U1") (pin "35") (pinfunction "GPIO_23_35") (pintype "bidirectional"))
    )
    (net (code "64") (name "unconnected-(U1-GPIO_24-Pad36)") (class "Default")
      (node (ref "U1") (pin "36") (pinfunction "GPIO_24_36") (pintype "bidirectional"))
    )
    (net (code "65") (name "unconnected-(U1-GPIO_25-Pad37)") (class "Default")
      (node (ref "U1") (pin "37") (pinfunction "GPIO_25_37") (pintype "bidirectional"))
    )
    (net (code "66") (name "unconnected-(U1-GPIO_26_(ADC0)-Pad40)") (class "Default")
      (node (ref "U1") (pin "40") (pinfunction "GPIO_26_(ADC0)_40") (pintype "bidirectional"))
    )
    (net (code "67") (name "unconnected-(U1-GPIO_28_(ADC2)-Pad42)") (class "Default")
      (node (ref "U1") (pin "42") (pinfunction "GPIO_28_(ADC2)_42") (pintype "bidirectional"))
    )
    (net (code "68") (name "unconnected-(U1-GPIO_29_(ADC3)-Pad43)") (class "Default")
      (node (ref "U1") (pin "43") (pinfunction "GPIO_29_(ADC3)_43") (pintype "bidirectional"))
    )
    (net (code "69") (name "unconnected-(U1-SWCLK-Pad24)") (class "Default")
      (node (ref "U1") (pin "24") (pinfunction "SWCLK_24") (pintype "output"))
    )
    (net (code "70") (name "unconnected-(U1-SWDIO-Pad25)") (class "Default")
      (node (ref "U1") (pin "25") (pinfunction "SWDIO_25") (pintype "bidirectional"))
    )
    (net (code "71") (name "unconnected-(U4-1IN+-Pad3)") (class "Default")
      (node (ref "U4") (pin "3") (pinfunction "1IN+_3") (pintype "input+no_connect"))
    )
    (net (code "72") (name "unconnected-(U4-1IN--Pad2)") (class "Default")
      (node (ref "U4") (pin "2") (pinfunction "1IN-_2") (pintype "input+no_connect"))
    )
    (net (code "73") (name "unconnected-(U4-1OUT-Pad1)") (class "Default")
      (node (ref "U4") (pin "1") (pinfunction "1OUT_1") (pintype "output"))
    )
  )
)
